# blink1mk2_v2c4.net
KiCad netlist of a schematic drawn in EAGLE
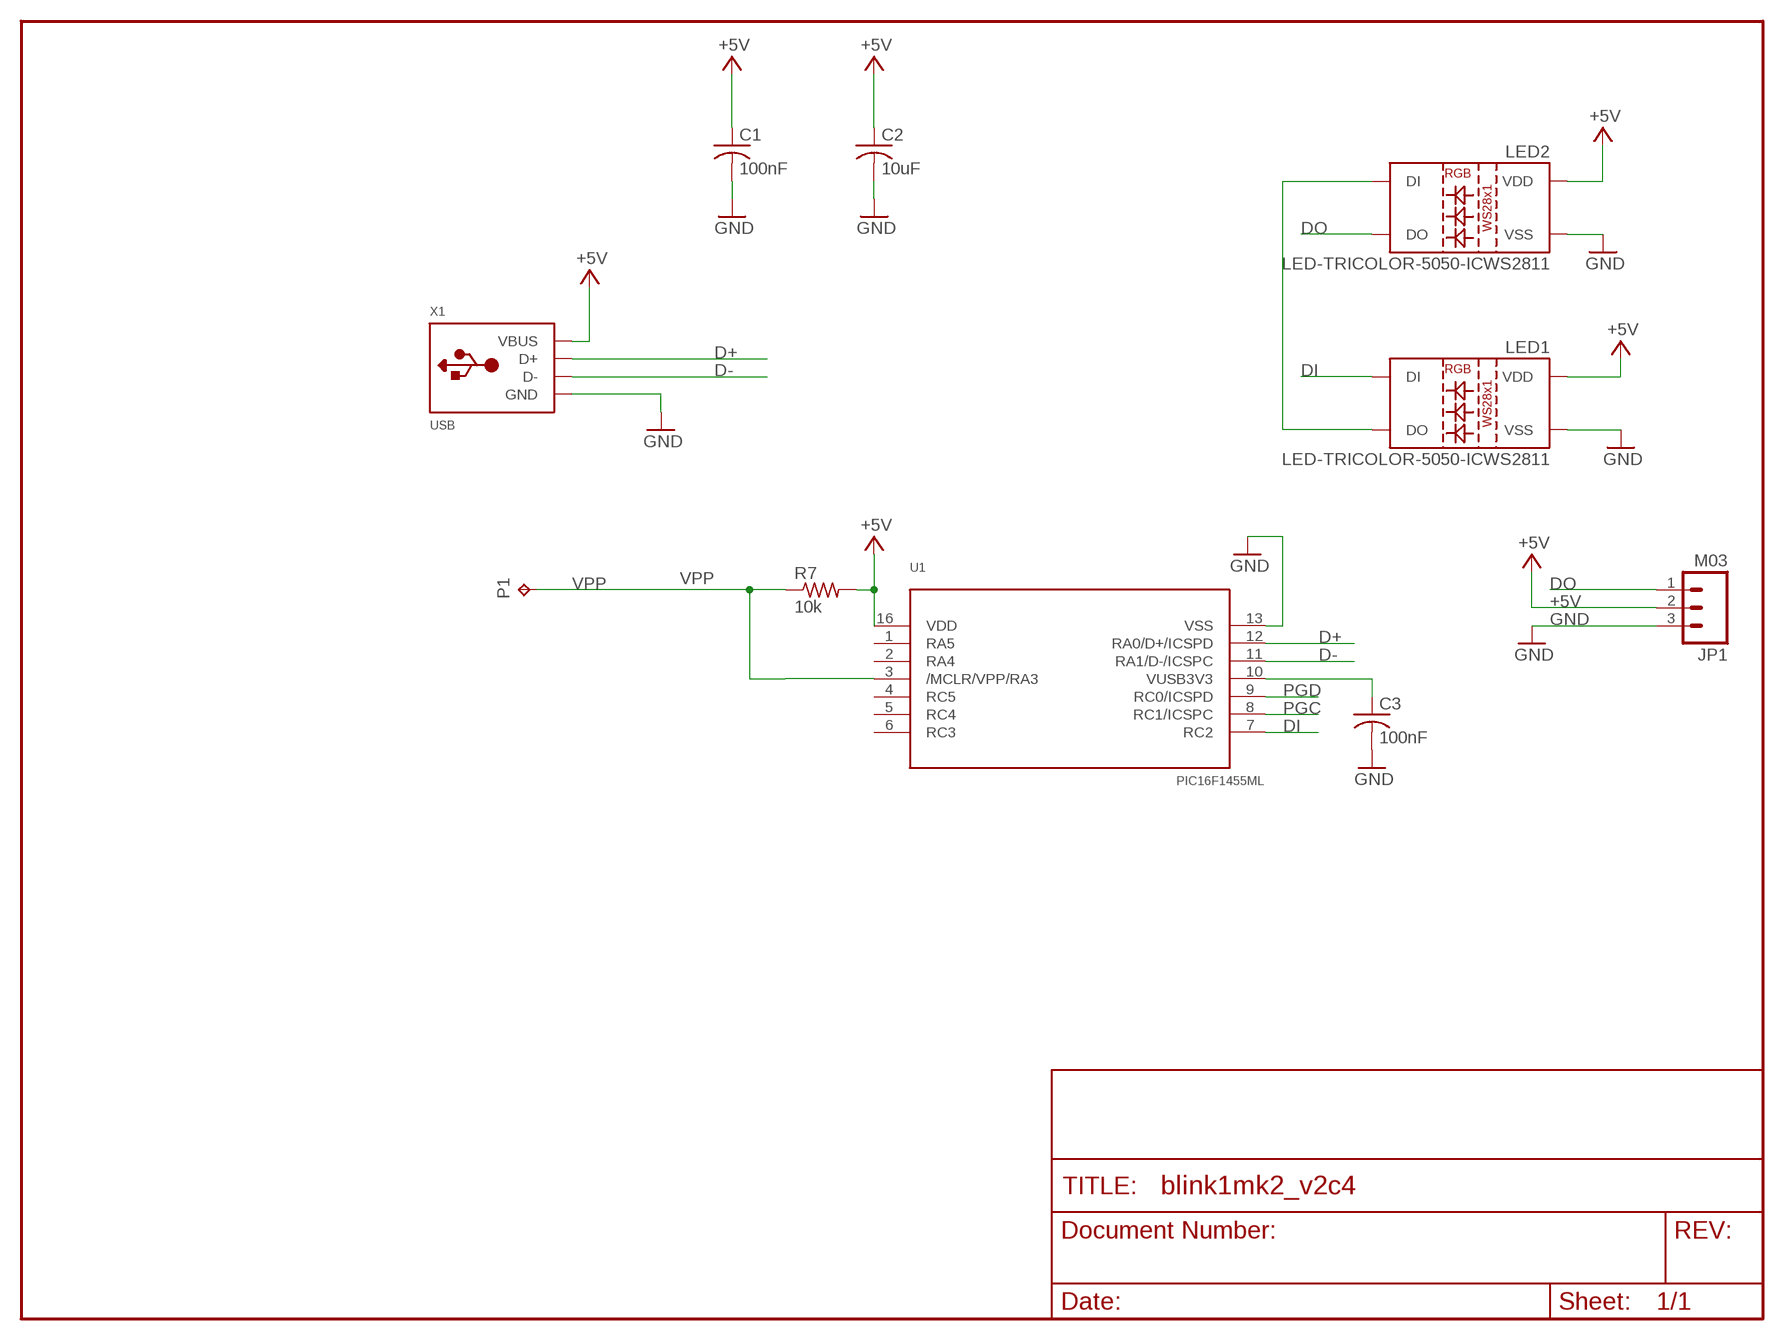
[diagram p0: schematic, sheet 1]

(export (version "E")
  (design (tool "Eeschema 10.0.6"))
  (components
    (comp (ref "C1")
      (value "100nF")
      (footprint "eagle-import:C0603")
      (libsource (lib "eagle-import") (part "C-USC0603"))
    )
    (comp (ref "C2")
      (value "10uF")
      (footprint "eagle-import:C0603")
      (libsource (lib "eagle-import") (part "C-USC0603"))
    )
    (comp (ref "C3")
      (value "100nF")
      (footprint "eagle-import:C0603")
      (libsource (lib "eagle-import") (part "C-USC0603"))
    )
    (comp (ref "JP1")
      (value "M03")
      (footprint "eagle-import:1X03-1.27MM")
      (libsource (lib "eagle-import") (part "M03"))
    )
    (comp (ref "LED1")
      (value "LED-TRICOLOR-5050-ICWS2811")
      (footprint "eagle-import:LED-TRICOLOR-5050-IC")
      (libsource (lib "eagle-import") (part "LED-TRICOLOR-5050-ICWS2811"))
    )
    (comp (ref "LED2")
      (value "LED-TRICOLOR-5050-ICWS2811")
      (footprint "eagle-import:LED-TRICOLOR-5050-IC")
      (libsource (lib "eagle-import") (part "LED-TRICOLOR-5050-ICWS2811"))
    )
    (comp (ref "P1")
      (value "TPTP11SQ")
      (footprint "eagle-import:TP11SQ")
      (libsource (lib "eagle-import") (part "TPTP11SQ"))
    )
    (comp (ref "R7")
      (value "10k")
      (footprint "eagle-import:R0603")
      (libsource (lib "eagle-import") (part "R-US_R0603"))
    )
    (comp (ref "U1")
      (value "PIC16F1455ML")
      (footprint "eagle-import:QFN16_4X4")
      (libsource (lib "eagle-import") (part "PIC16F1455ML"))
    )
    (comp (ref "X1")
      (value "USB")
      (footprint "eagle-import:MOLEX-48037-1000")
      (libsource (lib "eagle-import") (part "USB"))
    )
  )
  (nets
    (net (code "1") (name "+5V") (class "Default")
      (node (ref "C1") (pin "1") (pinfunction "1_1") (pintype "passive"))
      (node (ref "C2") (pin "1") (pinfunction "1_1") (pintype "passive"))
      (node (ref "JP1") (pin "2") (pinfunction "2_2") (pintype "passive"))
      (node (ref "LED1") (pin "3") (pinfunction "VDD_3") (pintype "bidirectional"))
      (node (ref "LED1") (pin "5") (pinfunction "VDD_5") (pintype "bidirectional"))
      (node (ref "LED2") (pin "3") (pinfunction "VDD_3") (pintype "bidirectional"))
      (node (ref "LED2") (pin "5") (pinfunction "VDD_5") (pintype "bidirectional"))
      (node (ref "R7") (pin "2") (pinfunction "2_2") (pintype "passive"))
      (node (ref "U1") (pin "16") (pinfunction "VDD_16") (pintype "bidirectional"))
      (node (ref "X1") (pin "1") (pinfunction "VBUS_1") (pintype "power_in"))
    )
    (net (code "2") (name "/D+") (class "Default")
      (node (ref "U1") (pin "12") (pinfunction "RA0/D+/ICSPD_12") (pintype "bidirectional"))
      (node (ref "X1") (pin "3") (pinfunction "D+_3") (pintype "bidirectional"))
    )
    (net (code "3") (name "/D-") (class "Default")
      (node (ref "U1") (pin "11") (pinfunction "RA1/D-/ICSPC_11") (pintype "bidirectional"))
      (node (ref "X1") (pin "2") (pinfunction "D-_2") (pintype "bidirectional"))
    )
    (net (code "4") (name "/DI") (class "Default")
      (node (ref "LED1") (pin "2") (pinfunction "DI_2") (pintype "bidirectional"))
      (node (ref "U1") (pin "7") (pinfunction "RC2_7") (pintype "bidirectional"))
    )
    (net (code "5") (name "/DO") (class "Default")
      (node (ref "JP1") (pin "1") (pinfunction "1_1") (pintype "passive"))
      (node (ref "LED2") (pin "1") (pinfunction "DO_1") (pintype "bidirectional"))
    )
    (net (code "6") (name "/PGC") (class "Default")
      (node (ref "U1") (pin "8") (pinfunction "RC1/ICSPC_8") (pintype "bidirectional"))
    )
    (net (code "7") (name "/PGD") (class "Default")
      (node (ref "U1") (pin "9") (pinfunction "RC0/ICSPD_9") (pintype "bidirectional"))
    )
    (net (code "8") (name "/VPP") (class "Default")
      (node (ref "P1") (pin "TP") (pinfunction "TP_TP") (pintype "input"))
      (node (ref "R7") (pin "1") (pinfunction "1_1") (pintype "passive"))
      (node (ref "U1") (pin "3") (pinfunction "/MCLR/VPP/RA3_3") (pintype "bidirectional"))
    )
    (net (code "9") (name "GND") (class "Default")
      (node (ref "C1") (pin "2") (pinfunction "2_2") (pintype "passive"))
      (node (ref "C2") (pin "2") (pinfunction "2_2") (pintype "passive"))
      (node (ref "C3") (pin "2") (pinfunction "2_2") (pintype "passive"))
      (node (ref "JP1") (pin "3") (pinfunction "3_3") (pintype "passive"))
      (node (ref "LED1") (pin "6") (pinfunction "VSS_6") (pintype "bidirectional"))
      (node (ref "LED2") (pin "6") (pinfunction "VSS_6") (pintype "bidirectional"))
      (node (ref "U1") (pin "13") (pinfunction "VSS_13") (pintype "bidirectional"))
      (node (ref "X1") (pin "4") (pinfunction "GND_4") (pintype "power_in"))
    )
    (net (code "10") (name "Net-(LED1-DO)") (class "Default")
      (node (ref "LED1") (pin "1") (pinfunction "DO_1") (pintype "bidirectional"))
      (node (ref "LED2") (pin "2") (pinfunction "DI_2") (pintype "bidirectional"))
    )
    (net (code "11") (name "Net-(U1-VUSB3V3)") (class "Default")
      (node (ref "C3") (pin "1") (pinfunction "1_1") (pintype "passive"))
      (node (ref "U1") (pin "10") (pinfunction "VUSB3V3_10") (pintype "bidirectional"))
    )
    (net (code "12") (name "unconnected-(U1-RA4-Pad2)") (class "Default")
      (node (ref "U1") (pin "2") (pinfunction "RA4_2") (pintype "bidirectional"))
    )
    (net (code "13") (name "unconnected-(U1-RA5-Pad1)") (class "Default")
      (node (ref "U1") (pin "1") (pinfunction "RA5_1") (pintype "bidirectional"))
    )
    (net (code "14") (name "unconnected-(U1-RC3-Pad6)") (class "Default")
      (node (ref "U1") (pin "6") (pinfunction "RC3_6") (pintype "bidirectional"))
    )
    (net (code "15") (name "unconnected-(U1-RC4-Pad5)") (class "Default")
      (node (ref "U1") (pin "5") (pinfunction "RC4_5") (pintype "bidirectional"))
    )
    (net (code "16") (name "unconnected-(U1-RC5-Pad4)") (class "Default")
      (node (ref "U1") (pin "4") (pinfunction "RC5_4") (pintype "bidirectional"))
    )
  )
)
